# PowerRegulation.net
KiCad netlist of a schematic drawn in Altium Designer
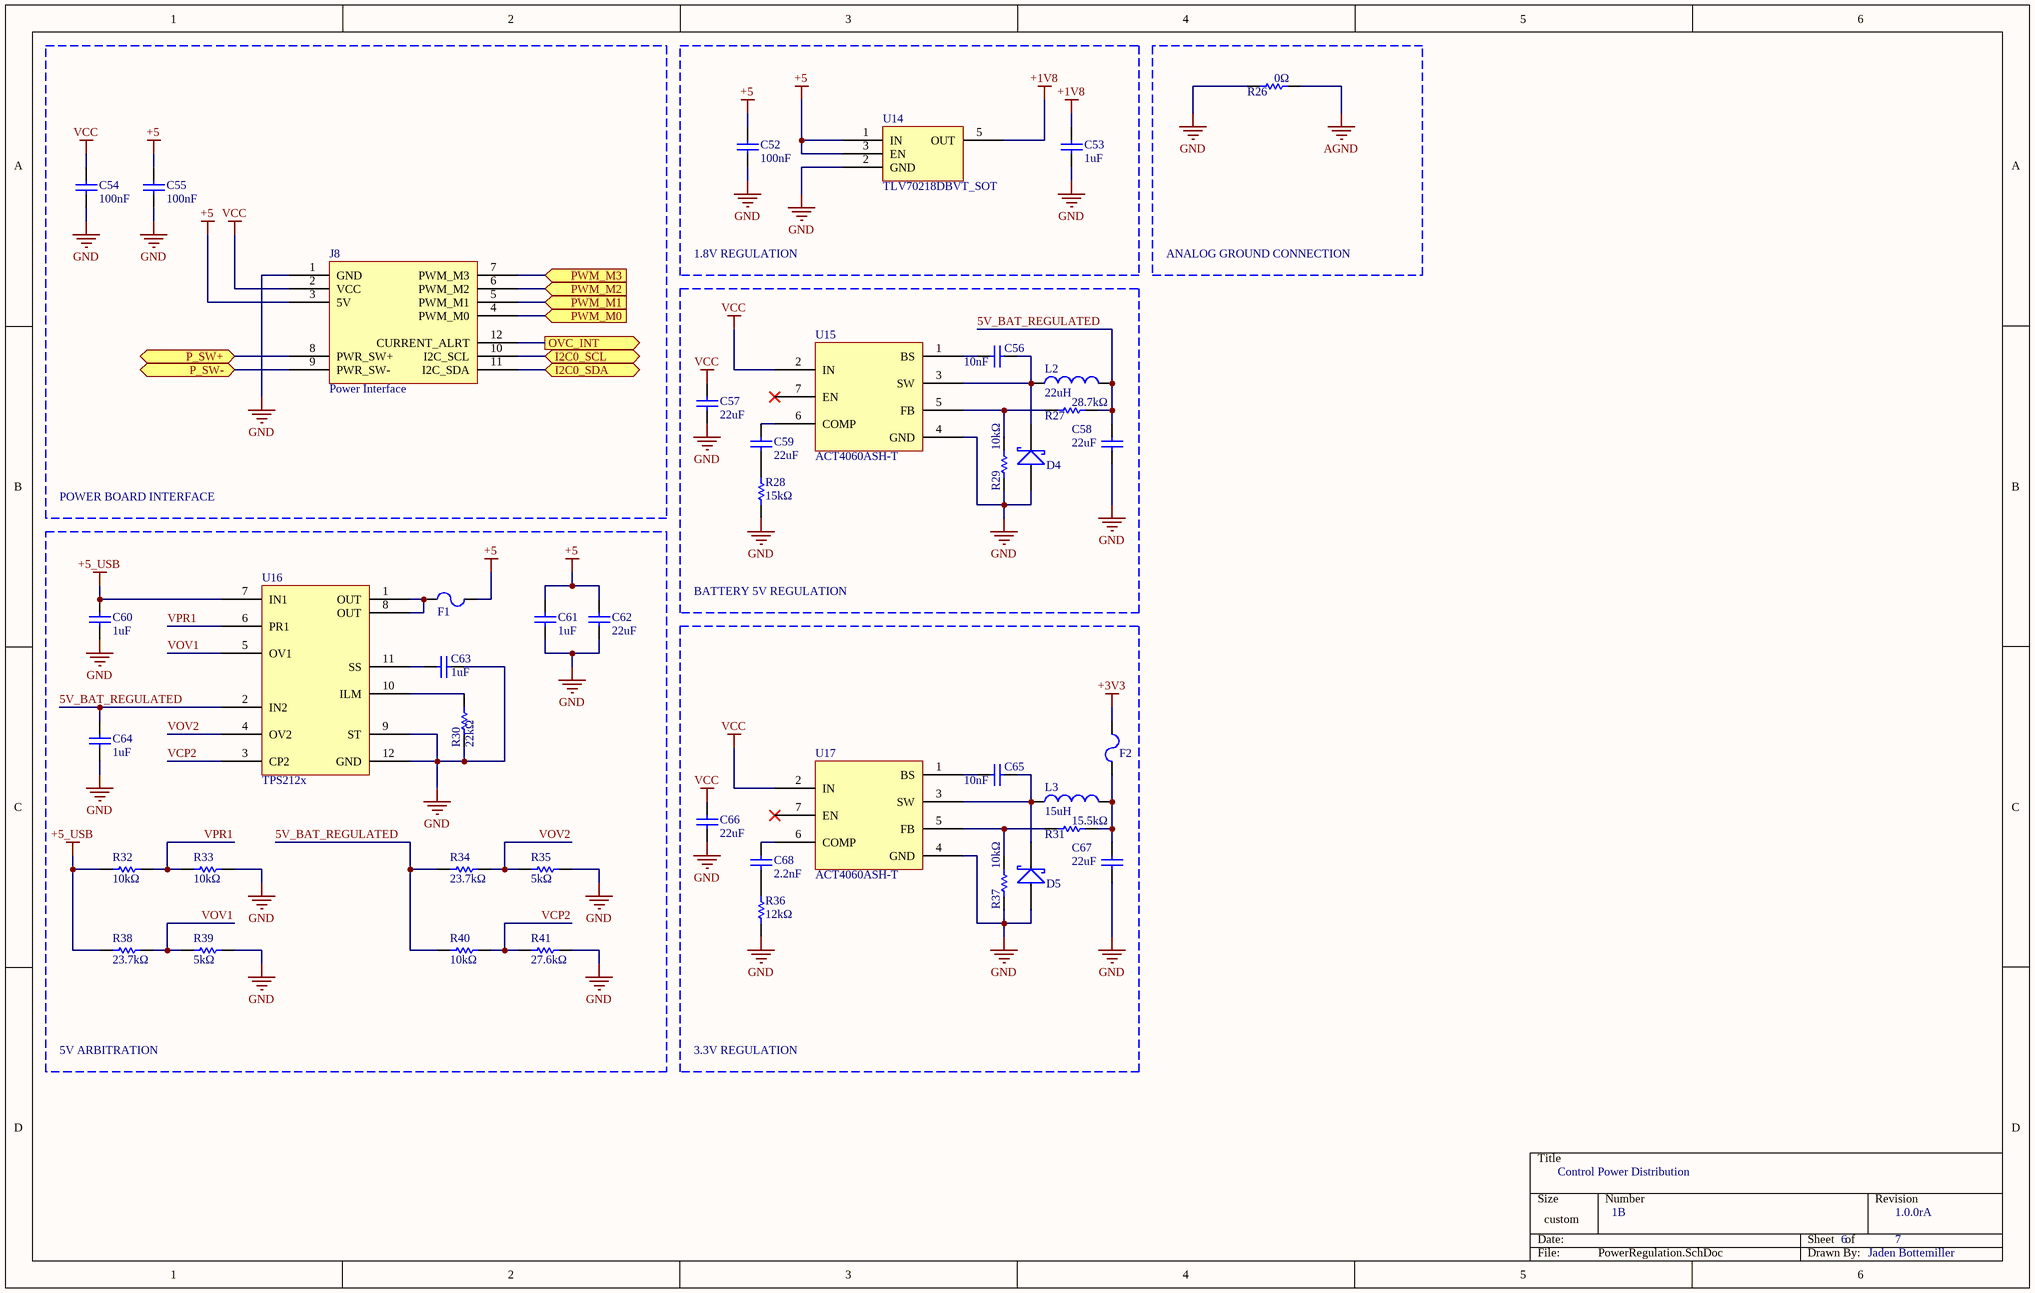
[diagram p0: PowerRegulation.SchDoc]

(export (version "E")
  (design (tool "Eeschema 10.0.6"))
  (components
    (comp (ref "C52")
      (value "100nF")
      (description "Standard Capacitor")
      (fields (field (name "Comment") "CAP"))
      (libsource (lib "NikoboticsLib") (part "CAP"))
    )
    (comp (ref "C53")
      (value "1uF")
      (description "Standard Capacitor")
      (fields (field (name "Comment") "CAP"))
      (libsource (lib "NikoboticsLib") (part "CAP"))
    )
    (comp (ref "C54")
      (value "100nF")
      (description "Standard Capacitor")
      (fields (field (name "Comment") "CAP"))
      (libsource (lib "NikoboticsLib") (part "CAP"))
    )
    (comp (ref "C55")
      (value "100nF")
      (description "Standard Capacitor")
      (fields (field (name "Comment") "CAP"))
      (libsource (lib "NikoboticsLib") (part "CAP"))
    )
    (comp (ref "C56")
      (value "10nF")
      (description "Standard Capacitor")
      (fields (field (name "Comment") "CAP"))
      (libsource (lib "NikoboticsLib") (part "CAP"))
    )
    (comp (ref "C57")
      (value "22uF")
      (description "Standard Capacitor")
      (fields (field (name "Comment") "CAP"))
      (libsource (lib "NikoboticsLib") (part "CAP"))
    )
    (comp (ref "C58")
      (value "22uF")
      (description "Standard Capacitor")
      (fields (field (name "Comment") "CAP"))
      (libsource (lib "NikoboticsLib") (part "CAP"))
    )
    (comp (ref "C59")
      (value "22uF")
      (description "Standard Capacitor")
      (fields (field (name "Comment") "CAP"))
      (libsource (lib "NikoboticsLib") (part "CAP"))
    )
    (comp (ref "C60")
      (value "1uF")
      (description "Standard Capacitor")
      (fields (field (name "Comment") "CAP"))
      (libsource (lib "NikoboticsLib") (part "CAP"))
    )
    (comp (ref "C61")
      (value "1uF")
      (description "Standard Capacitor")
      (fields (field (name "Comment") "CAP"))
      (libsource (lib "NikoboticsLib") (part "CAP"))
    )
    (comp (ref "C62")
      (value "22uF")
      (description "Standard Capacitor")
      (fields (field (name "Comment") "CAP"))
      (libsource (lib "NikoboticsLib") (part "CAP"))
    )
    (comp (ref "C63")
      (value "1uF")
      (description "Standard Capacitor")
      (fields (field (name "Comment") "CAP"))
      (libsource (lib "NikoboticsLib") (part "CAP"))
    )
    (comp (ref "C64")
      (value "1uF")
      (description "Standard Capacitor")
      (fields (field (name "Comment") "CAP"))
      (libsource (lib "NikoboticsLib") (part "CAP"))
    )
    (comp (ref "C65")
      (value "10nF")
      (description "Standard Capacitor")
      (fields (field (name "Comment") "CAP"))
      (libsource (lib "NikoboticsLib") (part "CAP"))
    )
    (comp (ref "C66")
      (value "22uF")
      (description "Standard Capacitor")
      (fields (field (name "Comment") "CAP"))
      (libsource (lib "NikoboticsLib") (part "CAP"))
    )
    (comp (ref "C67")
      (value "22uF")
      (description "Standard Capacitor")
      (fields (field (name "Comment") "CAP"))
      (libsource (lib "NikoboticsLib") (part "CAP"))
    )
    (comp (ref "C68")
      (value "2.2nF")
      (description "Standard Capacitor")
      (fields (field (name "Comment") "CAP"))
      (libsource (lib "NikoboticsLib") (part "CAP"))
    )
    (comp (ref "D4")
      (value "Schottky Diode")
      (description "Standard Schottky Diode")
      (libsource (lib "NikoboticsLib") (part "DIODE_SCHOTTKY"))
    )
    (comp (ref "D5")
      (value "Schottky Diode")
      (description "Standard Schottky Diode")
      (libsource (lib "NikoboticsLib") (part "DIODE_SCHOTTKY"))
    )
    (comp (ref "F1")
      (value "FUSE")
      (description "Standard Fuse")
      (libsource (lib "NikoboticsLib") (part "FUSE"))
    )
    (comp (ref "F2")
      (value "FUSE")
      (description "Standard Fuse")
      (libsource (lib "NikoboticsLib") (part "FUSE"))
    )
    (comp (ref "J8")
      (value "Power Interface")
      (description "Interface between power board and control board.")
      (libsource (lib "NikoboticsLib") (part "PDB_INTERFACE"))
    )
    (comp (ref "L2")
      (value "22uH")
      (description "Standard Inductor")
      (fields (field (name "Comment") "IND"))
      (libsource (lib "NikoboticsLib") (part "IND"))
    )
    (comp (ref "L3")
      (value "15uH")
      (description "Standard Inductor")
      (fields (field (name "Comment") "IND"))
      (libsource (lib "NikoboticsLib") (part "IND"))
    )
    (comp (ref "R26")
      (value "0Ω")
      (description "Standard Resistor")
      (fields (field (name "Comment") "RES"))
      (libsource (lib "NikoboticsLib") (part "RES"))
    )
    (comp (ref "R27")
      (value "28.7kΩ")
      (description "Standard Resistor")
      (fields (field (name "Comment") "RES"))
      (libsource (lib "NikoboticsLib") (part "RES"))
    )
    (comp (ref "R28")
      (value "15kΩ")
      (description "Standard Resistor")
      (fields (field (name "Comment") "RES"))
      (libsource (lib "NikoboticsLib") (part "RES"))
    )
    (comp (ref "R29")
      (value "10kΩ")
      (description "Standard Resistor")
      (fields (field (name "Comment") "RES"))
      (libsource (lib "NikoboticsLib") (part "RES"))
    )
    (comp (ref "R30")
      (value "22kΩ")
      (description "Standard Resistor")
      (fields (field (name "Comment") "RES"))
      (libsource (lib "NikoboticsLib") (part "RES"))
    )
    (comp (ref "R31")
      (value "15.5kΩ")
      (description "Standard Resistor")
      (fields (field (name "Comment") "RES"))
      (libsource (lib "NikoboticsLib") (part "RES"))
    )
    (comp (ref "R32")
      (value "10kΩ")
      (description "Standard Resistor")
      (fields (field (name "Comment") "RES"))
      (libsource (lib "NikoboticsLib") (part "RES"))
    )
    (comp (ref "R33")
      (value "10kΩ")
      (description "Standard Resistor")
      (fields (field (name "Comment") "RES"))
      (libsource (lib "NikoboticsLib") (part "RES"))
    )
    (comp (ref "R34")
      (value "23.7kΩ")
      (description "Standard Resistor")
      (fields (field (name "Comment") "RES"))
      (libsource (lib "NikoboticsLib") (part "RES"))
    )
    (comp (ref "R35")
      (value "5kΩ")
      (description "Standard Resistor")
      (fields (field (name "Comment") "RES"))
      (libsource (lib "NikoboticsLib") (part "RES"))
    )
    (comp (ref "R36")
      (value "12kΩ")
      (description "Standard Resistor")
      (fields (field (name "Comment") "RES"))
      (libsource (lib "NikoboticsLib") (part "RES"))
    )
    (comp (ref "R37")
      (value "10kΩ")
      (description "Standard Resistor")
      (fields (field (name "Comment") "RES"))
      (libsource (lib "NikoboticsLib") (part "RES"))
    )
    (comp (ref "R38")
      (value "23.7kΩ")
      (description "Standard Resistor")
      (fields (field (name "Comment") "RES"))
      (libsource (lib "NikoboticsLib") (part "RES"))
    )
    (comp (ref "R39")
      (value "5kΩ")
      (description "Standard Resistor")
      (fields (field (name "Comment") "RES"))
      (libsource (lib "NikoboticsLib") (part "RES"))
    )
    (comp (ref "R40")
      (value "10kΩ")
      (description "Standard Resistor")
      (fields (field (name "Comment") "RES"))
      (libsource (lib "NikoboticsLib") (part "RES"))
    )
    (comp (ref "R41")
      (value "27.6kΩ")
      (description "Standard Resistor")
      (fields (field (name "Comment") "RES"))
      (libsource (lib "NikoboticsLib") (part "RES"))
    )
    (comp (ref "U14")
      (value "TLV70218DBVT_SOT")
      (description "Linear Voltage Regulator IC Positive Fixed 1 Output  300mA \r\nSOT-23-5 ONLY (CHECK D/S FOR WSON)")
      (libsource (lib "NikoboticsLib") (part "TLV70218DBVT"))
    )
    (comp (ref "U15")
      (value "ACT4060ASH-T")
      (description "Buck Switching Regulator IC Positive Adjustable 1.293V 1 Output 2A")
      (libsource (lib "NikoboticsLib") (part "ACT4060ASH-T"))
    )
    (comp (ref "U16")
      (value "TPS212x")
      (description "General Purpose PMIC - PWR MGMT BATTERY MGMT")
      (libsource (lib "NikoboticsLib") (part "TPS212x"))
    )
    (comp (ref "U17")
      (value "ACT4060ASH-T")
      (description "Buck Switching Regulator IC Positive Adjustable 1.293V 1 Output 2A")
      (libsource (lib "NikoboticsLib") (part "ACT4060ASH-T"))
    )
  )
  (nets
    (net (code "1") (name "+1V8") (class "Default")
      (node (ref "C53") (pin "2") (pinfunction "2_2") (pintype "passive"))
      (node (ref "U14") (pin "5") (pinfunction "OUT_5") (pintype "power_in"))
    )
    (net (code "2") (name "+3V3") (class "Default")
      (node (ref "F2") (pin "2") (pinfunction "2_2") (pintype "passive"))
    )
    (net (code "3") (name "+5") (class "Default")
      (node (ref "C52") (pin "2") (pinfunction "2_2") (pintype "passive"))
      (node (ref "C55") (pin "2") (pinfunction "2_2") (pintype "passive"))
      (node (ref "C61") (pin "1") (pinfunction "1_1") (pintype "passive"))
      (node (ref "C62") (pin "1") (pinfunction "1_1") (pintype "passive"))
      (node (ref "F1") (pin "2") (pinfunction "2_2") (pintype "passive"))
      (node (ref "J8") (pin "3") (pinfunction "5V_3") (pintype "passive"))
      (node (ref "U14") (pin "1") (pinfunction "IN_1") (pintype "power_in"))
      (node (ref "U14") (pin "3") (pinfunction "EN_3") (pintype "passive"))
    )
    (net (code "4") (name "+5_USB") (class "Default")
      (node (ref "C60") (pin "1") (pinfunction "1_1") (pintype "passive"))
      (node (ref "R32") (pin "2") (pinfunction "2_2") (pintype "passive"))
      (node (ref "R38") (pin "2") (pinfunction "2_2") (pintype "passive"))
      (node (ref "U16") (pin "7") (pinfunction "IN1_7") (pintype "passive"))
    )
    (net (code "5") (name "/5V_BAT_REGULATED") (class "Default")
      (node (ref "C58") (pin "2") (pinfunction "2_2") (pintype "passive"))
      (node (ref "C64") (pin "1") (pinfunction "1_1") (pintype "passive"))
      (node (ref "L2") (pin "2") (pinfunction "2_2") (pintype "passive"))
      (node (ref "R27") (pin "1") (pinfunction "1_1") (pintype "passive"))
      (node (ref "R34") (pin "2") (pinfunction "2_2") (pintype "passive"))
      (node (ref "R40") (pin "2") (pinfunction "2_2") (pintype "passive"))
      (node (ref "U16") (pin "2") (pinfunction "IN2_2") (pintype "passive"))
    )
    (net (code "6") (name "/I2C0_SCL") (class "Default")
      (node (ref "J8") (pin "10") (pinfunction "I2C_SCL_10") (pintype "passive"))
    )
    (net (code "7") (name "/I2C0_SDA") (class "Default")
      (node (ref "J8") (pin "11") (pinfunction "I2C_SDA_11") (pintype "passive"))
    )
    (net (code "8") (name "/OVC_INT") (class "Default")
      (node (ref "J8") (pin "12") (pinfunction "CURRENT_ALRT_12") (pintype "passive"))
    )
    (net (code "9") (name "/PWM_M0") (class "Default")
      (node (ref "J8") (pin "4") (pinfunction "PWM_M0_4") (pintype "passive"))
    )
    (net (code "10") (name "/PWM_M1") (class "Default")
      (node (ref "J8") (pin "5") (pinfunction "PWM_M1_5") (pintype "passive"))
    )
    (net (code "11") (name "/PWM_M2") (class "Default")
      (node (ref "J8") (pin "6") (pinfunction "PWM_M2_6") (pintype "passive"))
    )
    (net (code "12") (name "/PWM_M3") (class "Default")
      (node (ref "J8") (pin "7") (pinfunction "PWM_M3_7") (pintype "passive"))
    )
    (net (code "13") (name "/P_SW+") (class "Default")
      (node (ref "J8") (pin "8") (pinfunction "PWR_SW+_8") (pintype "passive"))
    )
    (net (code "14") (name "/P_SW-") (class "Default")
      (node (ref "J8") (pin "9") (pinfunction "PWR_SW-_9") (pintype "passive"))
    )
    (net (code "15") (name "/VCP2") (class "Default")
      (node (ref "R40") (pin "1") (pinfunction "1_1") (pintype "passive"))
      (node (ref "R41") (pin "2") (pinfunction "2_2") (pintype "passive"))
      (node (ref "U16") (pin "3") (pinfunction "CP2_3") (pintype "passive"))
    )
    (net (code "16") (name "/VOV1") (class "Default")
      (node (ref "R38") (pin "1") (pinfunction "1_1") (pintype "passive"))
      (node (ref "R39") (pin "2") (pinfunction "2_2") (pintype "passive"))
      (node (ref "U16") (pin "5") (pinfunction "OV1_5") (pintype "passive"))
    )
    (net (code "17") (name "/VOV2") (class "Default")
      (node (ref "R34") (pin "1") (pinfunction "1_1") (pintype "passive"))
      (node (ref "R35") (pin "2") (pinfunction "2_2") (pintype "passive"))
      (node (ref "U16") (pin "4") (pinfunction "OV2_4") (pintype "passive"))
    )
    (net (code "18") (name "/VPR1") (class "Default")
      (node (ref "R32") (pin "1") (pinfunction "1_1") (pintype "passive"))
      (node (ref "R33") (pin "2") (pinfunction "2_2") (pintype "passive"))
      (node (ref "U16") (pin "6") (pinfunction "PR1_6") (pintype "passive"))
    )
    (net (code "19") (name "AGND") (class "Default")
      (node (ref "R26") (pin "1") (pinfunction "1_1") (pintype "passive"))
    )
    (net (code "20") (name "GND") (class "Default")
      (node (ref "C52") (pin "1") (pinfunction "1_1") (pintype "passive"))
      (node (ref "C53") (pin "1") (pinfunction "1_1") (pintype "passive"))
      (node (ref "C54") (pin "1") (pinfunction "1_1") (pintype "passive"))
      (node (ref "C55") (pin "1") (pinfunction "1_1") (pintype "passive"))
      (node (ref "C57") (pin "1") (pinfunction "1_1") (pintype "passive"))
      (node (ref "C58") (pin "1") (pinfunction "1_1") (pintype "passive"))
      (node (ref "C60") (pin "2") (pinfunction "2_2") (pintype "passive"))
      (node (ref "C61") (pin "2") (pinfunction "2_2") (pintype "passive"))
      (node (ref "C62") (pin "2") (pinfunction "2_2") (pintype "passive"))
      (node (ref "C63") (pin "1") (pinfunction "1_1") (pintype "passive"))
      (node (ref "C64") (pin "2") (pinfunction "2_2") (pintype "passive"))
      (node (ref "C66") (pin "1") (pinfunction "1_1") (pintype "passive"))
      (node (ref "C67") (pin "1") (pinfunction "1_1") (pintype "passive"))
      (node (ref "D4") (pin "2") (pinfunction "A_2") (pintype "passive"))
      (node (ref "D5") (pin "2") (pinfunction "A_2") (pintype "passive"))
      (node (ref "J8") (pin "1") (pinfunction "GND_1") (pintype "passive"))
      (node (ref "R26") (pin "2") (pinfunction "2_2") (pintype "passive"))
      (node (ref "R28") (pin "1") (pinfunction "1_1") (pintype "passive"))
      (node (ref "R29") (pin "2") (pinfunction "2_2") (pintype "passive"))
      (node (ref "R30") (pin "1") (pinfunction "1_1") (pintype "passive"))
      (node (ref "R33") (pin "1") (pinfunction "1_1") (pintype "passive"))
      (node (ref "R35") (pin "1") (pinfunction "1_1") (pintype "passive"))
      (node (ref "R36") (pin "1") (pinfunction "1_1") (pintype "passive"))
      (node (ref "R37") (pin "2") (pinfunction "2_2") (pintype "passive"))
      (node (ref "R39") (pin "1") (pinfunction "1_1") (pintype "passive"))
      (node (ref "R41") (pin "1") (pinfunction "1_1") (pintype "passive"))
      (node (ref "U14") (pin "2") (pinfunction "GND_2") (pintype "power_in"))
      (node (ref "U15") (pin "4") (pinfunction "GND_4") (pintype "passive"))
      (node (ref "U16") (pin "12") (pinfunction "GND_12") (pintype "passive"))
      (node (ref "U16") (pin "9") (pinfunction "ST_9") (pintype "passive"))
      (node (ref "U17") (pin "4") (pinfunction "GND_4") (pintype "passive"))
    )
    (net (code "21") (name "Net-(C59-Pad1)") (class "Default")
      (node (ref "C59") (pin "1") (pinfunction "1_1") (pintype "passive"))
      (node (ref "R28") (pin "2") (pinfunction "2_2") (pintype "passive"))
    )
    (net (code "22") (name "Net-(C67-Pad2)") (class "Default")
      (node (ref "C67") (pin "2") (pinfunction "2_2") (pintype "passive"))
      (node (ref "F2") (pin "1") (pinfunction "1_1") (pintype "passive"))
      (node (ref "L3") (pin "2") (pinfunction "2_2") (pintype "passive"))
      (node (ref "R31") (pin "1") (pinfunction "1_1") (pintype "passive"))
    )
    (net (code "23") (name "Net-(C68-Pad1)") (class "Default")
      (node (ref "C68") (pin "1") (pinfunction "1_1") (pintype "passive"))
      (node (ref "R36") (pin "2") (pinfunction "2_2") (pintype "passive"))
    )
    (net (code "24") (name "Net-(D4-K)") (class "Default")
      (node (ref "C56") (pin "2") (pinfunction "2_2") (pintype "passive"))
      (node (ref "D4") (pin "1") (pinfunction "K_1") (pintype "passive"))
      (node (ref "L2") (pin "1") (pinfunction "1_1") (pintype "passive"))
      (node (ref "U15") (pin "3") (pinfunction "SW_3") (pintype "passive"))
    )
    (net (code "25") (name "Net-(D5-K)") (class "Default")
      (node (ref "C65") (pin "2") (pinfunction "2_2") (pintype "passive"))
      (node (ref "D5") (pin "1") (pinfunction "K_1") (pintype "passive"))
      (node (ref "L3") (pin "1") (pinfunction "1_1") (pintype "passive"))
      (node (ref "U17") (pin "3") (pinfunction "SW_3") (pintype "passive"))
    )
    (net (code "26") (name "Net-(F1-Pad1)") (class "Default")
      (node (ref "F1") (pin "1") (pinfunction "1_1") (pintype "passive"))
      (node (ref "U16") (pin "1") (pinfunction "OUT_1") (pintype "passive"))
      (node (ref "U16") (pin "8") (pinfunction "OUT_8") (pintype "passive"))
    )
    (net (code "27") (name "Net-(U15-BS)") (class "Default")
      (node (ref "C56") (pin "1") (pinfunction "1_1") (pintype "passive"))
      (node (ref "U15") (pin "1") (pinfunction "BS_1") (pintype "passive"))
    )
    (net (code "28") (name "Net-(U15-COMP)") (class "Default")
      (node (ref "C59") (pin "2") (pinfunction "2_2") (pintype "passive"))
      (node (ref "U15") (pin "6") (pinfunction "COMP_6") (pintype "passive"))
    )
    (net (code "29") (name "Net-(U15-FB)") (class "Default")
      (node (ref "R27") (pin "2") (pinfunction "2_2") (pintype "passive"))
      (node (ref "R29") (pin "1") (pinfunction "1_1") (pintype "passive"))
      (node (ref "U15") (pin "5") (pinfunction "FB_5") (pintype "passive"))
    )
    (net (code "30") (name "Net-(U16-ILM)") (class "Default")
      (node (ref "R30") (pin "2") (pinfunction "2_2") (pintype "passive"))
      (node (ref "U16") (pin "10") (pinfunction "ILM_10") (pintype "passive"))
    )
    (net (code "31") (name "Net-(U16-SS)") (class "Default")
      (node (ref "C63") (pin "2") (pinfunction "2_2") (pintype "passive"))
      (node (ref "U16") (pin "11") (pinfunction "SS_11") (pintype "passive"))
    )
    (net (code "32") (name "Net-(U17-BS)") (class "Default")
      (node (ref "C65") (pin "1") (pinfunction "1_1") (pintype "passive"))
      (node (ref "U17") (pin "1") (pinfunction "BS_1") (pintype "passive"))
    )
    (net (code "33") (name "Net-(U17-COMP)") (class "Default")
      (node (ref "C68") (pin "2") (pinfunction "2_2") (pintype "passive"))
      (node (ref "U17") (pin "6") (pinfunction "COMP_6") (pintype "passive"))
    )
    (net (code "34") (name "Net-(U17-FB)") (class "Default")
      (node (ref "R31") (pin "2") (pinfunction "2_2") (pintype "passive"))
      (node (ref "R37") (pin "1") (pinfunction "1_1") (pintype "passive"))
      (node (ref "U17") (pin "5") (pinfunction "FB_5") (pintype "passive"))
    )
    (net (code "35") (name "VCC") (class "Default")
      (node (ref "C54") (pin "2") (pinfunction "2_2") (pintype "passive"))
      (node (ref "C57") (pin "2") (pinfunction "2_2") (pintype "passive"))
      (node (ref "C66") (pin "2") (pinfunction "2_2") (pintype "passive"))
      (node (ref "J8") (pin "2") (pinfunction "VCC_2") (pintype "passive"))
      (node (ref "U15") (pin "2") (pinfunction "IN_2") (pintype "passive"))
      (node (ref "U17") (pin "2") (pinfunction "IN_2") (pintype "passive"))
    )
    (net (code "36") (name "unconnected-(U14-NC-Pad4)") (class "Default")
      (node (ref "U14") (pin "4") (pinfunction "NC_4") (pintype "passive"))
    )
    (net (code "37") (name "unconnected-(U15-EN-Pad7)") (class "Default")
      (node (ref "U15") (pin "7") (pinfunction "EN_7") (pintype "passive+no_connect"))
    )
    (net (code "38") (name "unconnected-(U15-NC-Pad8)") (class "Default")
      (node (ref "U15") (pin "8") (pinfunction "NC_8") (pintype "passive"))
    )
    (net (code "39") (name "unconnected-(U17-EN-Pad7)") (class "Default")
      (node (ref "U17") (pin "7") (pinfunction "EN_7") (pintype "passive+no_connect"))
    )
    (net (code "40") (name "unconnected-(U17-NC-Pad8)") (class "Default")
      (node (ref "U17") (pin "8") (pinfunction "NC_8") (pintype "passive"))
    )
  )
)
